# PIO_Isolation.net
KiCad netlist of a schematic drawn in Altium Designer
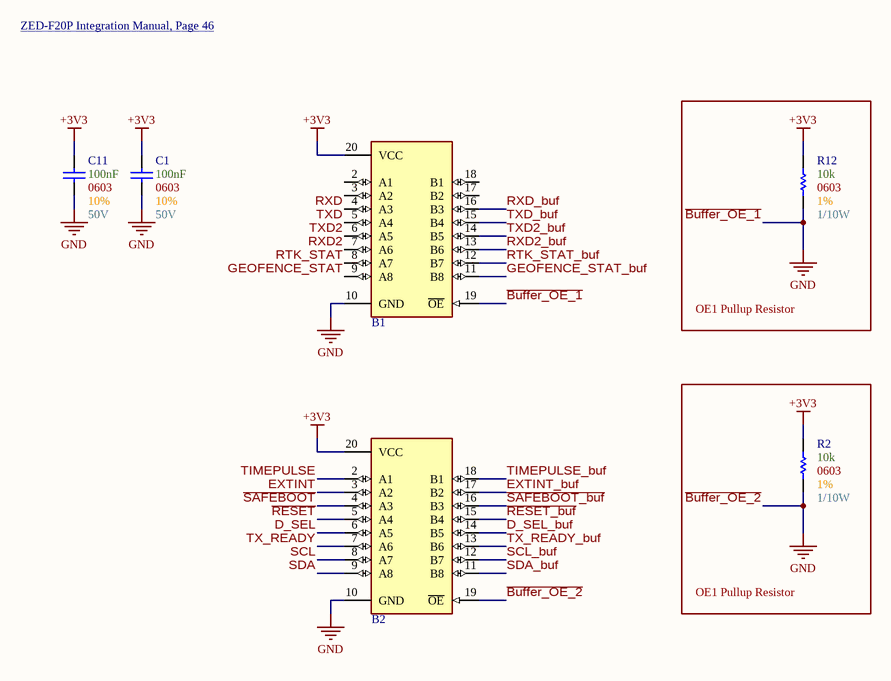
[diagram p0: PIO Isolation.SchDoc]

(export (version "E")
  (design (tool "Eeschema 10.0.6"))
  (components
    (comp (ref "B1")
      (value "[Isolation Buffer] Bus Switch x8")
      (footprint "[Isolation Buffer] Bus Switch x8")
      (description "SN74CBTLV3245APWR")
      (libsource (lib "ICs") (part "[Isolation Buffer] Bus Switch x8"))
    )
    (comp (ref "B2")
      (value "[Isolation Buffer] Bus Switch x8")
      (footprint "[Isolation Buffer] Bus Switch x8")
      (description "SN74CBTLV3245APWR")
      (libsource (lib "ICs") (part "[Isolation Buffer] Bus Switch x8"))
    )
    (comp (ref "C1")
      (value "[Cap] 0603 0.1uF 10% 50V")
      (footprint "[Cap] SMD 0603")
      (description "CL10B104KB8NNNC")
      (fields
        (field (name "MAX VOLTAGE") "50V")
        (field (name "SIZE PACKAGE") "0603")
        (field (name "TOLERANCE") "10%")
        (field (name "CAPACITANCE") "100nF")
      )
      (libsource (lib "Capacitors") (part "[Cap] 0603 0.1uF 10% 50V"))
    )
    (comp (ref "C11")
      (value "[Cap] 0603 0.1uF 10% 50V")
      (footprint "[Cap] SMD 0603")
      (description "CL10B104KB8NNNC")
      (fields
        (field (name "MAX VOLTAGE") "50V")
        (field (name "SIZE PACKAGE") "0603")
        (field (name "TOLERANCE") "10%")
        (field (name "CAPACITANCE") "100nF")
      )
      (libsource (lib "Capacitors") (part "[Cap] 0603 0.1uF 10% 50V"))
    )
    (comp (ref "R2")
      (value "[10k] SMD 0603 1% 1/8W")
      (footprint "[Res] SMD 0603")
      (description "RMCF0603FT10K0")
      (fields
        (field (name "WATTAGE") "1/10W")
        (field (name "TOLERANCE") "1%")
        (field (name "RESISTANCE") "10k")
        (field (name "SIZE PACKAGE") "0603")
      )
      (libsource (lib "Resistors") (part "[10k] SMD 0603 1% 1/8W"))
    )
    (comp (ref "R12")
      (value "[10k] SMD 0603 1% 1/8W")
      (footprint "[Res] SMD 0603")
      (description "RMCF0603FT10K0")
      (fields
        (field (name "WATTAGE") "1/10W")
        (field (name "TOLERANCE") "1%")
        (field (name "RESISTANCE") "10k")
        (field (name "SIZE PACKAGE") "0603")
      )
      (libsource (lib "Resistors") (part "[10k] SMD 0603 1% 1/8W"))
    )
  )
  (nets
    (net (code "1") (name "+3V3") (class "Default")
      (node (ref "B1") (pin "20") (pinfunction "VCC_20") (pintype "power_in"))
      (node (ref "B2") (pin "20") (pinfunction "VCC_20") (pintype "power_in"))
      (node (ref "C1") (pin "2") (pinfunction "2_2") (pintype "passive"))
      (node (ref "C11") (pin "2") (pinfunction "2_2") (pintype "passive"))
      (node (ref "R12") (pin "2") (pinfunction "2_2") (pintype "passive"))
      (node (ref "R2") (pin "2") (pinfunction "2_2") (pintype "passive"))
    )
    (net (code "2") (name "/D_SEL") (class "Default")
      (node (ref "B2") (pin "6") (pinfunction "A5_6") (pintype "bidirectional"))
    )
    (net (code "3") (name "/D_SEL_buf") (class "Default")
      (node (ref "B2") (pin "14") (pinfunction "B5_14") (pintype "bidirectional"))
    )
    (net (code "4") (name "/EXTINT") (class "Default")
      (node (ref "B2") (pin "3") (pinfunction "A2_3") (pintype "bidirectional"))
    )
    (net (code "5") (name "/EXTINT_buf") (class "Default")
      (node (ref "B2") (pin "17") (pinfunction "B2_17") (pintype "bidirectional"))
    )
    (net (code "6") (name "/GEOFENCE_STAT") (class "Default")
      (node (ref "B1") (pin "9") (pinfunction "A8_9") (pintype "bidirectional"))
    )
    (net (code "7") (name "/GEOFENCE_STAT_buf") (class "Default")
      (node (ref "B1") (pin "11") (pinfunction "B8_11") (pintype "bidirectional"))
    )
    (net (code "8") (name "/RESET") (class "Default")
      (node (ref "B2") (pin "5") (pinfunction "A4_5") (pintype "bidirectional"))
    )
    (net (code "9") (name "/RESET_buf") (class "Default")
      (node (ref "B2") (pin "15") (pinfunction "B4_15") (pintype "bidirectional"))
    )
    (net (code "10") (name "/RTK_STAT") (class "Default")
      (node (ref "B1") (pin "8") (pinfunction "A7_8") (pintype "bidirectional"))
    )
    (net (code "11") (name "/RTK_STAT_buf") (class "Default")
      (node (ref "B1") (pin "12") (pinfunction "B7_12") (pintype "bidirectional"))
    )
    (net (code "12") (name "/RXD") (class "Default")
      (node (ref "B1") (pin "4") (pinfunction "A3_4") (pintype "bidirectional"))
    )
    (net (code "13") (name "/RXD2") (class "Default")
      (node (ref "B1") (pin "7") (pinfunction "A6_7") (pintype "bidirectional"))
    )
    (net (code "14") (name "/RXD2_buf") (class "Default")
      (node (ref "B1") (pin "13") (pinfunction "B6_13") (pintype "bidirectional"))
    )
    (net (code "15") (name "/RXD_buf") (class "Default")
      (node (ref "B1") (pin "16") (pinfunction "B3_16") (pintype "bidirectional"))
    )
    (net (code "16") (name "/SAFEBOOT") (class "Default")
      (node (ref "B2") (pin "4") (pinfunction "A3_4") (pintype "bidirectional"))
    )
    (net (code "17") (name "/SAFEBOOT_buf") (class "Default")
      (node (ref "B2") (pin "16") (pinfunction "B3_16") (pintype "bidirectional"))
    )
    (net (code "18") (name "/SCL") (class "Default")
      (node (ref "B2") (pin "8") (pinfunction "A7_8") (pintype "bidirectional"))
    )
    (net (code "19") (name "/SCL_buf") (class "Default")
      (node (ref "B2") (pin "12") (pinfunction "B7_12") (pintype "bidirectional"))
    )
    (net (code "20") (name "/SDA") (class "Default")
      (node (ref "B2") (pin "9") (pinfunction "A8_9") (pintype "bidirectional"))
    )
    (net (code "21") (name "/SDA_buf") (class "Default")
      (node (ref "B2") (pin "11") (pinfunction "B8_11") (pintype "bidirectional"))
    )
    (net (code "22") (name "/TIMEPULSE") (class "Default")
      (node (ref "B2") (pin "2") (pinfunction "A1_2") (pintype "bidirectional"))
    )
    (net (code "23") (name "/TIMEPULSE_buf") (class "Default")
      (node (ref "B2") (pin "18") (pinfunction "B1_18") (pintype "bidirectional"))
    )
    (net (code "24") (name "/TXD") (class "Default")
      (node (ref "B1") (pin "5") (pinfunction "A4_5") (pintype "bidirectional"))
    )
    (net (code "25") (name "/TXD2") (class "Default")
      (node (ref "B1") (pin "6") (pinfunction "A5_6") (pintype "bidirectional"))
    )
    (net (code "26") (name "/TXD2_buf") (class "Default")
      (node (ref "B1") (pin "14") (pinfunction "B5_14") (pintype "bidirectional"))
    )
    (net (code "27") (name "/TXD_buf") (class "Default")
      (node (ref "B1") (pin "15") (pinfunction "B4_15") (pintype "bidirectional"))
    )
    (net (code "28") (name "/TX_READY") (class "Default")
      (node (ref "B2") (pin "7") (pinfunction "A6_7") (pintype "bidirectional"))
    )
    (net (code "29") (name "/TX_READY_buf") (class "Default")
      (node (ref "B2") (pin "13") (pinfunction "B6_13") (pintype "bidirectional"))
    )
    (net (code "30") (name "GND") (class "Default")
      (node (ref "B1") (pin "10") (pinfunction "GND_10") (pintype "power_in"))
      (node (ref "B1") (pin "19") (pinfunction "~{OE}_19") (pintype "input"))
      (node (ref "B2") (pin "10") (pinfunction "GND_10") (pintype "power_in"))
      (node (ref "B2") (pin "19") (pinfunction "~{OE}_19") (pintype "input"))
      (node (ref "C1") (pin "1") (pinfunction "1_1") (pintype "passive"))
      (node (ref "C11") (pin "1") (pinfunction "1_1") (pintype "passive"))
      (node (ref "R12") (pin "1") (pinfunction "1_1") (pintype "passive"))
      (node (ref "R2") (pin "1") (pinfunction "1_1") (pintype "passive"))
    )
    (net (code "31") (name "unconnected-(B1-A1-Pad2)") (class "Default")
      (node (ref "B1") (pin "2") (pinfunction "A1_2") (pintype "bidirectional"))
    )
    (net (code "32") (name "unconnected-(B1-A2-Pad3)") (class "Default")
      (node (ref "B1") (pin "3") (pinfunction "A2_3") (pintype "bidirectional"))
    )
    (net (code "33") (name "unconnected-(B1-B1-Pad18)") (class "Default")
      (node (ref "B1") (pin "18") (pinfunction "B1_18") (pintype "bidirectional"))
    )
    (net (code "34") (name "unconnected-(B1-B2-Pad17)") (class "Default")
      (node (ref "B1") (pin "17") (pinfunction "B2_17") (pintype "bidirectional"))
    )
  )
)
